# aa_battery.net
KiCad netlist of a schematic drawn in EAGLE
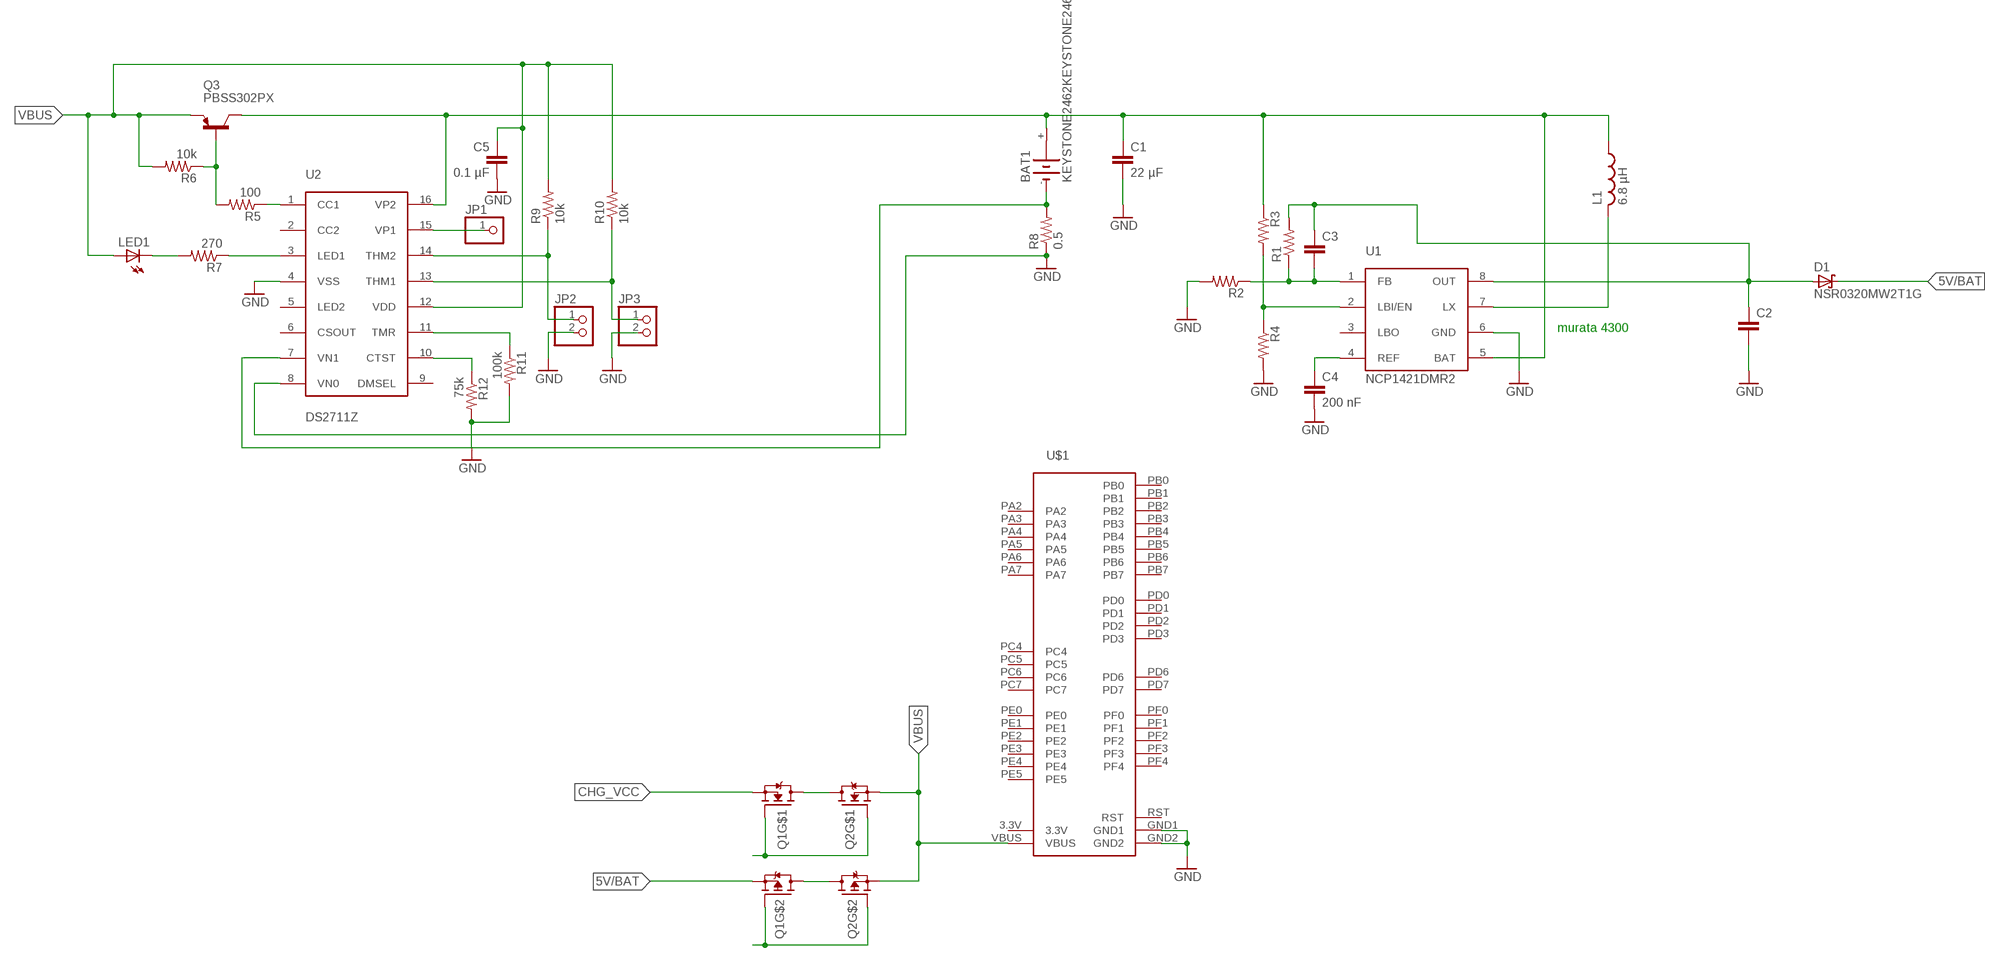
[diagram p0: schematic, sheet 1]

(export (version "E")
  (design (tool "Eeschema 10.0.6"))
  (components
    (comp (ref "BAT1")
      (value "KEYSTONE2462KEYSTONE2462")
      (footprint "eagle-import:KEYSTONE2462")
      (libsource (lib "eagle-import") (part "KEYSTONE2462KEYSTONE2462"))
    )
    (comp (ref "C1")
      (value "22 µF")
      (footprint "eagle-import:C0805")
      (libsource (lib "eagle-import") (part "C-EUC0805"))
    )
    (comp (ref "C2")
      (value "C-EUC1210")
      (footprint "eagle-import:C1210")
      (libsource (lib "eagle-import") (part "C-EUC1210"))
    )
    (comp (ref "C3")
      (value "C-EUC0805")
      (footprint "eagle-import:C0805")
      (libsource (lib "eagle-import") (part "C-EUC0805"))
    )
    (comp (ref "C4")
      (value "200 nF")
      (footprint "eagle-import:C0805")
      (libsource (lib "eagle-import") (part "C-EUC0805"))
    )
    (comp (ref "C5")
      (value "0.1 µF")
      (footprint "eagle-import:C0805")
      (libsource (lib "eagle-import") (part "C-EUC0805"))
    )
    (comp (ref "D1")
      (value "NSR0320MW2T1G")
      (footprint "eagle-import:SOD323")
      (libsource (lib "eagle-import") (part "SCHOTTKY-DIODENSR0320MW2T1G"))
    )
    (comp (ref "JP1")
      (value "PINHD-1X1")
      (footprint "eagle-import:1X01")
      (libsource (lib "eagle-import") (part "PINHD-1X1"))
    )
    (comp (ref "JP2")
      (value "PINHD-1X2")
      (footprint "eagle-import:1X02")
      (libsource (lib "eagle-import") (part "PINHD-1X2"))
    )
    (comp (ref "JP3")
      (value "PINHD-1X2")
      (footprint "eagle-import:1X02")
      (libsource (lib "eagle-import") (part "PINHD-1X2"))
    )
    (comp (ref "L1")
      (value "6.8 µH")
      (footprint "eagle-import:MURATA4500")
      (libsource (lib "eagle-import") (part "L-USMURATA4500"))
    )
    (comp (ref "LED1")
      (value "LED5MM")
      (footprint "eagle-import:LED5MM")
      (libsource (lib "eagle-import") (part "LED5MM"))
    )
    (comp (ref "Q1")
      (value "DMC2038LVT-7")
      (footprint "eagle-import:TSOT26")
      (libsource (lib "eagle-import") (part "DMC2038LVT-7"))
    )
    (comp (ref "Q2")
      (value "DMC2038LVT-7")
      (footprint "eagle-import:TSOT26")
      (libsource (lib "eagle-import") (part "DMC2038LVT-7"))
    )
    (comp (ref "Q3")
      (value "PBSS302PX")
      (footprint "eagle-import:SOT89-BCE")
      (libsource (lib "eagle-import") (part "-PNP-SOT98-BCEBF621"))
    )
    (comp (ref "R1")
      (value "R-US_R0805")
      (footprint "eagle-import:R0805")
      (libsource (lib "eagle-import") (part "R-US_R0805"))
    )
    (comp (ref "R2")
      (value "R-US_R0805")
      (footprint "eagle-import:R0805")
      (libsource (lib "eagle-import") (part "R-US_R0805"))
    )
    (comp (ref "R3")
      (value "R-US_R0805")
      (footprint "eagle-import:R0805")
      (libsource (lib "eagle-import") (part "R-US_R0805"))
    )
    (comp (ref "R4")
      (value "R-US_R0805")
      (footprint "eagle-import:R0805")
      (libsource (lib "eagle-import") (part "R-US_R0805"))
    )
    (comp (ref "R5")
      (value "100")
      (footprint "eagle-import:R0805")
      (libsource (lib "eagle-import") (part "R-US_R0805"))
    )
    (comp (ref "R6")
      (value "10k")
      (footprint "eagle-import:R0805")
      (libsource (lib "eagle-import") (part "R-US_R0805"))
    )
    (comp (ref "R7")
      (value "270")
      (footprint "eagle-import:R0805")
      (libsource (lib "eagle-import") (part "R-US_R0805"))
    )
    (comp (ref "R8")
      (value "0.5")
      (footprint "eagle-import:R0805")
      (libsource (lib "eagle-import") (part "R-US_R0805"))
    )
    (comp (ref "R9")
      (value "10k")
      (footprint "eagle-import:R0805")
      (libsource (lib "eagle-import") (part "R-US_R0805"))
    )
    (comp (ref "R10")
      (value "10k")
      (footprint "eagle-import:R0805")
      (libsource (lib "eagle-import") (part "R-US_R0805"))
    )
    (comp (ref "R11")
      (value "100k")
      (footprint "eagle-import:R0805")
      (libsource (lib "eagle-import") (part "R-US_R0805"))
    )
    (comp (ref "R12")
      (value "75k")
      (footprint "eagle-import:R0805")
      (libsource (lib "eagle-import") (part "R-US_R0805"))
    )
    (comp (ref "U$1")
      (value "STELLARIS-LAUNCHPADSTELLARIS-LAUNCHPAD-XL")
      (footprint "eagle-import:LAUNCHPAD-XL")
      (libsource (lib "eagle-import") (part "STELLARIS-LAUNCHPADSTELLARIS-LAUNCHPAD-XL"))
    )
    (comp (ref "U1")
      (value "NCP1421DMR2")
      (footprint "eagle-import:MICRO8")
      (libsource (lib "eagle-import") (part "NCP1421DMR2"))
    )
    (comp (ref "U2")
      (value "DS2711Z")
      (footprint "eagle-import:SO16")
      (libsource (lib "eagle-import") (part "DS2711Z"))
    )
  )
  (nets
    (net (code "1") (name "/3.3V") (class "Default")
      (node (ref "U$1") (pin "3.3V") (pinfunction "3.3V_3.3V") (pintype "power_in"))
    )
    (net (code "2") (name "/RST") (class "Default")
      (node (ref "U$1") (pin "RST") (pinfunction "RST_RST") (pintype "power_in"))
    )
    (net (code "3") (name "5V{slash}BAT") (class "Default")
      (node (ref "D1") (pin "C") (pinfunction "C_C") (pintype "passive"))
      (node (ref "Q1") (pin "2") (pinfunction "S1_2") (pintype "passive"))
    )
    (net (code "4") (name "CHG_VCC") (class "Default")
      (node (ref "Q1") (pin "5") (pinfunction "S_5") (pintype "passive"))
    )
    (net (code "5") (name "GND") (class "Default")
      (node (ref "C1") (pin "2") (pinfunction "2_2") (pintype "passive"))
      (node (ref "C2") (pin "2") (pinfunction "2_2") (pintype "passive"))
      (node (ref "C4") (pin "2") (pinfunction "2_2") (pintype "passive"))
      (node (ref "C5") (pin "2") (pinfunction "2_2") (pintype "passive"))
      (node (ref "JP2") (pin "2") (pinfunction "2_2") (pintype "passive"))
      (node (ref "JP3") (pin "2") (pinfunction "2_2") (pintype "passive"))
      (node (ref "R11") (pin "2") (pinfunction "2_2") (pintype "passive"))
      (node (ref "R12") (pin "2") (pinfunction "2_2") (pintype "passive"))
      (node (ref "R2") (pin "2") (pinfunction "2_2") (pintype "passive"))
      (node (ref "R4") (pin "2") (pinfunction "2_2") (pintype "passive"))
      (node (ref "R8") (pin "1") (pinfunction "1_1") (pintype "passive"))
      (node (ref "U$1") (pin "GND1") (pinfunction "GND1_GND1") (pintype "bidirectional"))
      (node (ref "U$1") (pin "GND2") (pinfunction "GND2_GND2") (pintype "power_in"))
      (node (ref "U1") (pin "6") (pinfunction "GND_6") (pintype "bidirectional"))
      (node (ref "U2") (pin "4") (pinfunction "VSS_4") (pintype "bidirectional"))
      (node (ref "U2") (pin "8") (pinfunction "VN0_8") (pintype "bidirectional"))
    )
    (net (code "6") (name "Net-(LED1-C)") (class "Default")
      (node (ref "LED1") (pin "K") (pinfunction "C_K") (pintype "passive"))
      (node (ref "R7") (pin "2") (pinfunction "2_2") (pintype "passive"))
    )
    (net (code "7") (name "Net-(Q1A-D)") (class "Default")
      (node (ref "Q1") (pin "6") (pinfunction "D_6") (pintype "passive"))
      (node (ref "Q2") (pin "6") (pinfunction "D_6") (pintype "passive"))
    )
    (net (code "8") (name "Net-(Q1A-G)") (class "Default")
      (node (ref "Q1") (pin "1") (pinfunction "G_1") (pintype "passive"))
      (node (ref "Q2") (pin "1") (pinfunction "G_1") (pintype "passive"))
    )
    (net (code "9") (name "Net-(Q1B-D1)") (class "Default")
      (node (ref "Q1") (pin "4") (pinfunction "D1_4") (pintype "passive"))
      (node (ref "Q2") (pin "4") (pinfunction "D1_4") (pintype "passive"))
    )
    (net (code "10") (name "Net-(Q1B-G1)") (class "Default")
      (node (ref "Q1") (pin "3") (pinfunction "G1_3") (pintype "passive"))
      (node (ref "Q2") (pin "3") (pinfunction "G1_3") (pintype "passive"))
    )
    (net (code "11") (name "Net-(Q3-PadB)") (class "Default")
      (node (ref "Q3") (pin "B") (pinfunction "B_B") (pintype "passive"))
      (node (ref "R5") (pin "2") (pinfunction "2_2") (pintype "passive"))
      (node (ref "R6") (pin "1") (pinfunction "1_1") (pintype "passive"))
    )
    (net (code "12") (name "Net-(U1-BAT)") (class "Default")
      (node (ref "BAT1") (pin "+") (pinfunction "+_+") (pintype "passive"))
      (node (ref "C1") (pin "1") (pinfunction "1_1") (pintype "passive"))
      (node (ref "L1") (pin "1") (pinfunction "1_1") (pintype "passive"))
      (node (ref "Q3") (pin "C") (pinfunction "C_C") (pintype "passive"))
      (node (ref "Q3") (pin "C@1") (pinfunction "C_C@1") (pintype "passive"))
      (node (ref "R3") (pin "1") (pinfunction "1_1") (pintype "passive"))
      (node (ref "U1") (pin "5") (pinfunction "BAT_5") (pintype "bidirectional"))
      (node (ref "U2") (pin "16") (pinfunction "VP2_16") (pintype "bidirectional"))
    )
    (net (code "13") (name "Net-(U1-FB)") (class "Default")
      (node (ref "C3") (pin "2") (pinfunction "2_2") (pintype "passive"))
      (node (ref "R1") (pin "1") (pinfunction "1_1") (pintype "passive"))
      (node (ref "R2") (pin "1") (pinfunction "1_1") (pintype "passive"))
      (node (ref "U1") (pin "1") (pinfunction "FB_1") (pintype "bidirectional"))
    )
    (net (code "14") (name "Net-(U1-LBI{slash}EN)") (class "Default")
      (node (ref "R3") (pin "2") (pinfunction "2_2") (pintype "passive"))
      (node (ref "R4") (pin "1") (pinfunction "1_1") (pintype "passive"))
      (node (ref "U1") (pin "2") (pinfunction "LBI/EN_2") (pintype "bidirectional"))
    )
    (net (code "15") (name "Net-(U1-LX)") (class "Default")
      (node (ref "L1") (pin "2") (pinfunction "2_2") (pintype "passive"))
      (node (ref "U1") (pin "7") (pinfunction "LX_7") (pintype "bidirectional"))
    )
    (net (code "16") (name "Net-(U1-OUT)") (class "Default")
      (node (ref "C2") (pin "1") (pinfunction "1_1") (pintype "passive"))
      (node (ref "C3") (pin "1") (pinfunction "1_1") (pintype "passive"))
      (node (ref "D1") (pin "A") (pinfunction "A_A") (pintype "passive"))
      (node (ref "R1") (pin "2") (pinfunction "2_2") (pintype "passive"))
      (node (ref "U1") (pin "8") (pinfunction "OUT_8") (pintype "bidirectional"))
    )
    (net (code "17") (name "Net-(U1-REF)") (class "Default")
      (node (ref "C4") (pin "1") (pinfunction "1_1") (pintype "passive"))
      (node (ref "U1") (pin "4") (pinfunction "REF_4") (pintype "bidirectional"))
    )
    (net (code "18") (name "Net-(U2-CC1)") (class "Default")
      (node (ref "R5") (pin "1") (pinfunction "1_1") (pintype "passive"))
      (node (ref "U2") (pin "1") (pinfunction "CC1_1") (pintype "bidirectional"))
    )
    (net (code "19") (name "Net-(U2-CTST)") (class "Default")
      (node (ref "R12") (pin "1") (pinfunction "1_1") (pintype "passive"))
      (node (ref "U2") (pin "10") (pinfunction "CTST_10") (pintype "bidirectional"))
    )
    (net (code "20") (name "Net-(U2-LED1)") (class "Default")
      (node (ref "R7") (pin "1") (pinfunction "1_1") (pintype "passive"))
      (node (ref "U2") (pin "3") (pinfunction "LED1_3") (pintype "bidirectional"))
    )
    (net (code "21") (name "Net-(U2-THM1)") (class "Default")
      (node (ref "JP3") (pin "1") (pinfunction "1_1") (pintype "passive"))
      (node (ref "R10") (pin "1") (pinfunction "1_1") (pintype "passive"))
      (node (ref "U2") (pin "13") (pinfunction "THM1_13") (pintype "bidirectional"))
    )
    (net (code "22") (name "Net-(U2-THM2)") (class "Default")
      (node (ref "JP2") (pin "1") (pinfunction "1_1") (pintype "passive"))
      (node (ref "R9") (pin "1") (pinfunction "1_1") (pintype "passive"))
      (node (ref "U2") (pin "14") (pinfunction "THM2_14") (pintype "bidirectional"))
    )
    (net (code "23") (name "Net-(U2-TMR)") (class "Default")
      (node (ref "R11") (pin "1") (pinfunction "1_1") (pintype "passive"))
      (node (ref "U2") (pin "11") (pinfunction "TMR_11") (pintype "bidirectional"))
    )
    (net (code "24") (name "Net-(U2-VN1)") (class "Default")
      (node (ref "BAT1") (pin "-") (pinfunction "-_-") (pintype "passive"))
      (node (ref "R8") (pin "2") (pinfunction "2_2") (pintype "passive"))
      (node (ref "U2") (pin "7") (pinfunction "VN1_7") (pintype "bidirectional"))
    )
    (net (code "25") (name "Net-(U2-VP1)") (class "Default")
      (node (ref "JP1") (pin "1") (pinfunction "1_1") (pintype "passive"))
      (node (ref "U2") (pin "15") (pinfunction "VP1_15") (pintype "bidirectional"))
    )
    (net (code "26") (name "VBUS") (class "Default")
      (node (ref "C5") (pin "1") (pinfunction "1_1") (pintype "passive"))
      (node (ref "LED1") (pin "A") (pinfunction "A_A") (pintype "passive"))
      (node (ref "Q2") (pin "2") (pinfunction "S1_2") (pintype "passive"))
      (node (ref "Q2") (pin "5") (pinfunction "S_5") (pintype "passive"))
      (node (ref "Q3") (pin "E") (pinfunction "E_E") (pintype "passive"))
      (node (ref "R10") (pin "2") (pinfunction "2_2") (pintype "passive"))
      (node (ref "R6") (pin "2") (pinfunction "2_2") (pintype "passive"))
      (node (ref "R9") (pin "2") (pinfunction "2_2") (pintype "passive"))
      (node (ref "U$1") (pin "VBUS") (pinfunction "VBUS_VBUS") (pintype "power_in"))
      (node (ref "U2") (pin "12") (pinfunction "VDD_12") (pintype "bidirectional"))
    )
    (net (code "27") (name "unconnected-(U$1-PadPA2)") (class "Default")
      (node (ref "U$1") (pin "PA2") (pinfunction "PA2_PA2") (pintype "bidirectional"))
    )
    (net (code "28") (name "unconnected-(U$1-PadPA3)") (class "Default")
      (node (ref "U$1") (pin "PA3") (pinfunction "PA3_PA3") (pintype "bidirectional"))
    )
    (net (code "29") (name "unconnected-(U$1-PadPA4)") (class "Default")
      (node (ref "U$1") (pin "PA4") (pinfunction "PA4_PA4") (pintype "bidirectional"))
    )
    (net (code "30") (name "unconnected-(U$1-PadPA5)") (class "Default")
      (node (ref "U$1") (pin "PA5") (pinfunction "PA5_PA5") (pintype "bidirectional"))
    )
    (net (code "31") (name "unconnected-(U$1-PadPA6)") (class "Default")
      (node (ref "U$1") (pin "PA6") (pinfunction "PA6_PA6") (pintype "bidirectional"))
    )
    (net (code "32") (name "unconnected-(U$1-PadPA7)") (class "Default")
      (node (ref "U$1") (pin "PA7") (pinfunction "PA7_PA7") (pintype "bidirectional"))
    )
    (net (code "33") (name "unconnected-(U$1-PadPB0)") (class "Default")
      (node (ref "U$1") (pin "PB0") (pinfunction "PB0_PB0") (pintype "bidirectional"))
    )
    (net (code "34") (name "unconnected-(U$1-PadPB1)") (class "Default")
      (node (ref "U$1") (pin "PB1") (pinfunction "PB1_PB1") (pintype "bidirectional"))
    )
    (net (code "35") (name "unconnected-(U$1-PadPB2)") (class "Default")
      (node (ref "U$1") (pin "PB2") (pinfunction "PB2_PB2") (pintype "bidirectional"))
    )
    (net (code "36") (name "unconnected-(U$1-PadPB3)") (class "Default")
      (node (ref "U$1") (pin "PB3") (pinfunction "PB3_PB3") (pintype "bidirectional"))
    )
    (net (code "37") (name "unconnected-(U$1-PadPB4)") (class "Default")
      (node (ref "U$1") (pin "PB4") (pinfunction "PB4_PB4") (pintype "bidirectional"))
    )
    (net (code "38") (name "unconnected-(U$1-PadPB5)") (class "Default")
      (node (ref "U$1") (pin "PB5") (pinfunction "PB5_PB5") (pintype "bidirectional"))
    )
    (net (code "39") (name "unconnected-(U$1-PadPB6)") (class "Default")
      (node (ref "U$1") (pin "PB6") (pinfunction "PB6_PB6") (pintype "bidirectional"))
    )
    (net (code "40") (name "unconnected-(U$1-PadPB7)") (class "Default")
      (node (ref "U$1") (pin "PB7") (pinfunction "PB7_PB7") (pintype "bidirectional"))
    )
    (net (code "41") (name "unconnected-(U$1-PadPC4)") (class "Default")
      (node (ref "U$1") (pin "PC4") (pinfunction "PC4_PC4") (pintype "bidirectional"))
    )
    (net (code "42") (name "unconnected-(U$1-PadPC5)") (class "Default")
      (node (ref "U$1") (pin "PC5") (pinfunction "PC5_PC5") (pintype "bidirectional"))
    )
    (net (code "43") (name "unconnected-(U$1-PadPC6)") (class "Default")
      (node (ref "U$1") (pin "PC6") (pinfunction "PC6_PC6") (pintype "bidirectional"))
    )
    (net (code "44") (name "unconnected-(U$1-PadPC7)") (class "Default")
      (node (ref "U$1") (pin "PC7") (pinfunction "PC7_PC7") (pintype "bidirectional"))
    )
    (net (code "45") (name "unconnected-(U$1-PadPD0)") (class "Default")
      (node (ref "U$1") (pin "PD0") (pinfunction "PD0_PD0") (pintype "bidirectional"))
    )
    (net (code "46") (name "unconnected-(U$1-PadPD1)") (class "Default")
      (node (ref "U$1") (pin "PD1") (pinfunction "PD1_PD1") (pintype "bidirectional"))
    )
    (net (code "47") (name "unconnected-(U$1-PadPD2)") (class "Default")
      (node (ref "U$1") (pin "PD2") (pinfunction "PD2_PD2") (pintype "bidirectional"))
    )
    (net (code "48") (name "unconnected-(U$1-PadPD3)") (class "Default")
      (node (ref "U$1") (pin "PD3") (pinfunction "PD3_PD3") (pintype "bidirectional"))
    )
    (net (code "49") (name "unconnected-(U$1-PadPD6)") (class "Default")
      (node (ref "U$1") (pin "PD6") (pinfunction "PD6_PD6") (pintype "bidirectional"))
    )
    (net (code "50") (name "unconnected-(U$1-PadPD7)") (class "Default")
      (node (ref "U$1") (pin "PD7") (pinfunction "PD7_PD7") (pintype "bidirectional"))
    )
    (net (code "51") (name "unconnected-(U$1-PadPE0)") (class "Default")
      (node (ref "U$1") (pin "PE0") (pinfunction "PE0_PE0") (pintype "bidirectional"))
    )
    (net (code "52") (name "unconnected-(U$1-PadPE1)") (class "Default")
      (node (ref "U$1") (pin "PE1") (pinfunction "PE1_PE1") (pintype "bidirectional"))
    )
    (net (code "53") (name "unconnected-(U$1-PadPE2)") (class "Default")
      (node (ref "U$1") (pin "PE2") (pinfunction "PE2_PE2") (pintype "bidirectional"))
    )
    (net (code "54") (name "unconnected-(U$1-PadPE3)") (class "Default")
      (node (ref "U$1") (pin "PE3") (pinfunction "PE3_PE3") (pintype "bidirectional"))
    )
    (net (code "55") (name "unconnected-(U$1-PadPE4)") (class "Default")
      (node (ref "U$1") (pin "PE4") (pinfunction "PE4_PE4") (pintype "bidirectional"))
    )
    (net (code "56") (name "unconnected-(U$1-PadPE5)") (class "Default")
      (node (ref "U$1") (pin "PE5") (pinfunction "PE5_PE5") (pintype "bidirectional"))
    )
    (net (code "57") (name "unconnected-(U$1-PadPF0)") (class "Default")
      (node (ref "U$1") (pin "PF0") (pinfunction "PF0_PF0") (pintype "bidirectional"))
    )
    (net (code "58") (name "unconnected-(U$1-PadPF1)") (class "Default")
      (node (ref "U$1") (pin "PF1") (pinfunction "PF1_PF1") (pintype "bidirectional"))
    )
    (net (code "59") (name "unconnected-(U$1-PadPF2)") (class "Default")
      (node (ref "U$1") (pin "PF2") (pinfunction "PF2_PF2") (pintype "bidirectional"))
    )
    (net (code "60") (name "unconnected-(U$1-PadPF3)") (class "Default")
      (node (ref "U$1") (pin "PF3") (pinfunction "PF3_PF3") (pintype "bidirectional"))
    )
    (net (code "61") (name "unconnected-(U$1-PadPF4)") (class "Default")
      (node (ref "U$1") (pin "PF4") (pinfunction "PF4_PF4") (pintype "bidirectional"))
    )
    (net (code "62") (name "unconnected-(U1-LBO-Pad3)") (class "Default")
      (node (ref "U1") (pin "3") (pinfunction "LBO_3") (pintype "bidirectional"))
    )
    (net (code "63") (name "unconnected-(U2-CC2-Pad2)") (class "Default")
      (node (ref "U2") (pin "2") (pinfunction "CC2_2") (pintype "bidirectional"))
    )
    (net (code "64") (name "unconnected-(U2-CSOUT-Pad6)") (class "Default")
      (node (ref "U2") (pin "6") (pinfunction "CSOUT_6") (pintype "bidirectional"))
    )
    (net (code "65") (name "unconnected-(U2-DMSEL-Pad9)") (class "Default")
      (node (ref "U2") (pin "9") (pinfunction "DMSEL_9") (pintype "bidirectional"))
    )
    (net (code "66") (name "unconnected-(U2-LED2-Pad5)") (class "Default")
      (node (ref "U2") (pin "5") (pinfunction "LED2_5") (pintype "bidirectional"))
    )
  )
)
